# 8Pin_Fuse.net
KiCad netlist of a schematic drawn in EAGLE
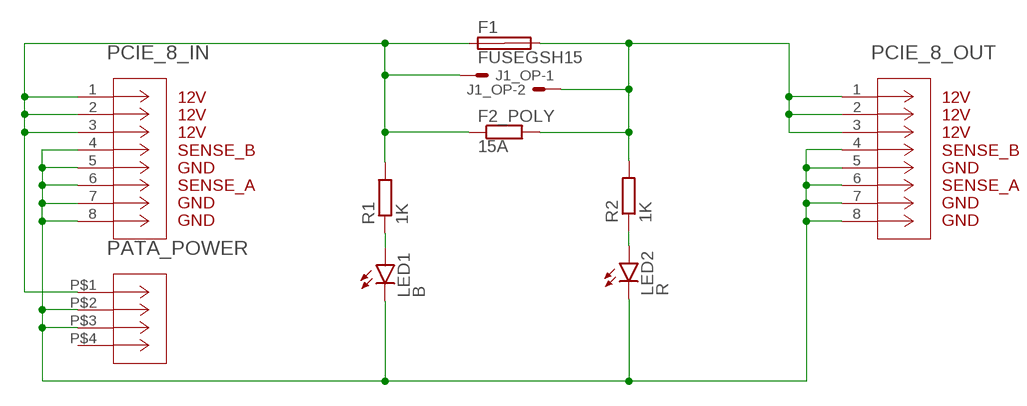
[diagram p0: schematic, sheet 1]

(export (version "E")
  (design (tool "Eeschema 10.0.6"))
  (components
    (comp (ref "F1")
      (value "FUSEGSH15")
      (footprint "eagle-import:SHK20Q")
      (libsource (lib "eagle-import") (part "SHK20Q"))
    )
    (comp (ref "F2_POLY")
      (value "15A")
      (footprint "eagle-import:M1206")
      (libsource (lib "eagle-import") (part "R-EU_M1206"))
    )
    (comp (ref "J1_OP")
      (value "87758-0216")
      (footprint "eagle-import:87758-0216")
      (fields (field (name "MF") "MOLEX"))
      (libsource (lib "eagle-import") (part "87758-0216"))
    )
    (comp (ref "LED1")
      (value "B")
      (footprint "eagle-import:SML0805")
      (libsource (lib "eagle-import") (part "LEDSML0805"))
    )
    (comp (ref "LED2")
      (value "R")
      (footprint "eagle-import:SML0805")
      (libsource (lib "eagle-import") (part "LEDSML0805"))
    )
    (comp (ref "PATA_POWER")
      (value "PATA_POWER")
      (footprint "eagle-import:PATA_POWER")
      (libsource (lib "eagle-import") (part "PATA_POWER"))
    )
    (comp (ref "PCIE_8_IN")
      (value "457180003A")
      (footprint "eagle-import:CON_457180003_MOL")
      (libsource (lib "eagle-import") (part "457180003A"))
    )
    (comp (ref "PCIE_8_OUT")
      (value "457180003A")
      (footprint "eagle-import:CON_457180003_MOL")
      (libsource (lib "eagle-import") (part "457180003A"))
    )
    (comp (ref "R1")
      (value "1K")
      (footprint "eagle-import:M0805")
      (libsource (lib "eagle-import") (part "R-EU_M0805"))
    )
    (comp (ref "R2")
      (value "1K")
      (footprint "eagle-import:M0805")
      (libsource (lib "eagle-import") (part "R-EU_M0805"))
    )
  )
  (nets
    (net (code "1") (name "Net-(J1_OPA-S)") (class "Default")
      (node (ref "F1") (pin "1A") (pinfunction "1A_1A") (pintype "passive"))
      (node (ref "F2_POLY") (pin "1") (pinfunction "1_1") (pintype "passive"))
      (node (ref "J1_OP") (pin "1") (pinfunction "S_1") (pintype "passive"))
      (node (ref "PATA_POWER") (pin "P$1") (pinfunction "1_P$1") (pintype "passive"))
      (node (ref "PCIE_8_IN") (pin "1") (pinfunction "1_1") (pintype "passive"))
      (node (ref "PCIE_8_IN") (pin "2") (pinfunction "2_2") (pintype "passive"))
      (node (ref "PCIE_8_IN") (pin "3") (pinfunction "3_3") (pintype "passive"))
      (node (ref "R1") (pin "2") (pinfunction "2_2") (pintype "passive"))
    )
    (net (code "2") (name "Net-(J1_OPB-S)") (class "Default")
      (node (ref "F1") (pin "2A") (pinfunction "2A_2A") (pintype "passive"))
      (node (ref "F2_POLY") (pin "2") (pinfunction "2_2") (pintype "passive"))
      (node (ref "J1_OP") (pin "2") (pinfunction "S_2") (pintype "passive"))
      (node (ref "PCIE_8_OUT") (pin "1") (pinfunction "1_1") (pintype "passive"))
      (node (ref "PCIE_8_OUT") (pin "2") (pinfunction "2_2") (pintype "passive"))
      (node (ref "PCIE_8_OUT") (pin "3") (pinfunction "3_3") (pintype "passive"))
      (node (ref "R2") (pin "2") (pinfunction "2_2") (pintype "passive"))
    )
    (net (code "3") (name "Net-(LED1-PadA)") (class "Default")
      (node (ref "LED1") (pin "A") (pinfunction "A_A") (pintype "passive"))
      (node (ref "R1") (pin "1") (pinfunction "1_1") (pintype "passive"))
    )
    (net (code "4") (name "Net-(LED2-PadA)") (class "Default")
      (node (ref "LED2") (pin "A") (pinfunction "A_A") (pintype "passive"))
      (node (ref "R2") (pin "1") (pinfunction "1_1") (pintype "passive"))
    )
    (net (code "5") (name "Net-(PATA_POWER-2)") (class "Default")
      (node (ref "LED1") (pin "C") (pinfunction "C_C") (pintype "passive"))
      (node (ref "LED2") (pin "C") (pinfunction "C_C") (pintype "passive"))
      (node (ref "PATA_POWER") (pin "P$2") (pinfunction "2_P$2") (pintype "passive"))
      (node (ref "PATA_POWER") (pin "P$3") (pinfunction "3_P$3") (pintype "passive"))
      (node (ref "PCIE_8_IN") (pin "4") (pinfunction "4_4") (pintype "passive"))
      (node (ref "PCIE_8_IN") (pin "5") (pinfunction "5_5") (pintype "passive"))
      (node (ref "PCIE_8_IN") (pin "6") (pinfunction "6_6") (pintype "passive"))
      (node (ref "PCIE_8_IN") (pin "7") (pinfunction "7_7") (pintype "passive"))
      (node (ref "PCIE_8_IN") (pin "8") (pinfunction "8_8") (pintype "passive"))
      (node (ref "PCIE_8_OUT") (pin "4") (pinfunction "4_4") (pintype "passive"))
      (node (ref "PCIE_8_OUT") (pin "5") (pinfunction "5_5") (pintype "passive"))
      (node (ref "PCIE_8_OUT") (pin "6") (pinfunction "6_6") (pintype "passive"))
      (node (ref "PCIE_8_OUT") (pin "7") (pinfunction "7_7") (pintype "passive"))
      (node (ref "PCIE_8_OUT") (pin "8") (pinfunction "8_8") (pintype "passive"))
    )
    (net (code "6") (name "unconnected-(F1-Pad1B)") (class "Default")
      (node (ref "F1") (pin "1B") (pinfunction "1B_1B") (pintype "passive"))
    )
    (net (code "7") (name "unconnected-(F1-Pad2B)") (class "Default")
      (node (ref "F1") (pin "2B") (pinfunction "2B_2B") (pintype "passive"))
    )
    (net (code "8") (name "unconnected-(PATA_POWER-4-PadP$4)") (class "Default")
      (node (ref "PATA_POWER") (pin "P$4") (pinfunction "4_P$4") (pintype "passive"))
    )
  )
)
